# schematic.net
KiCad netlist of a schematic drawn in EAGLE
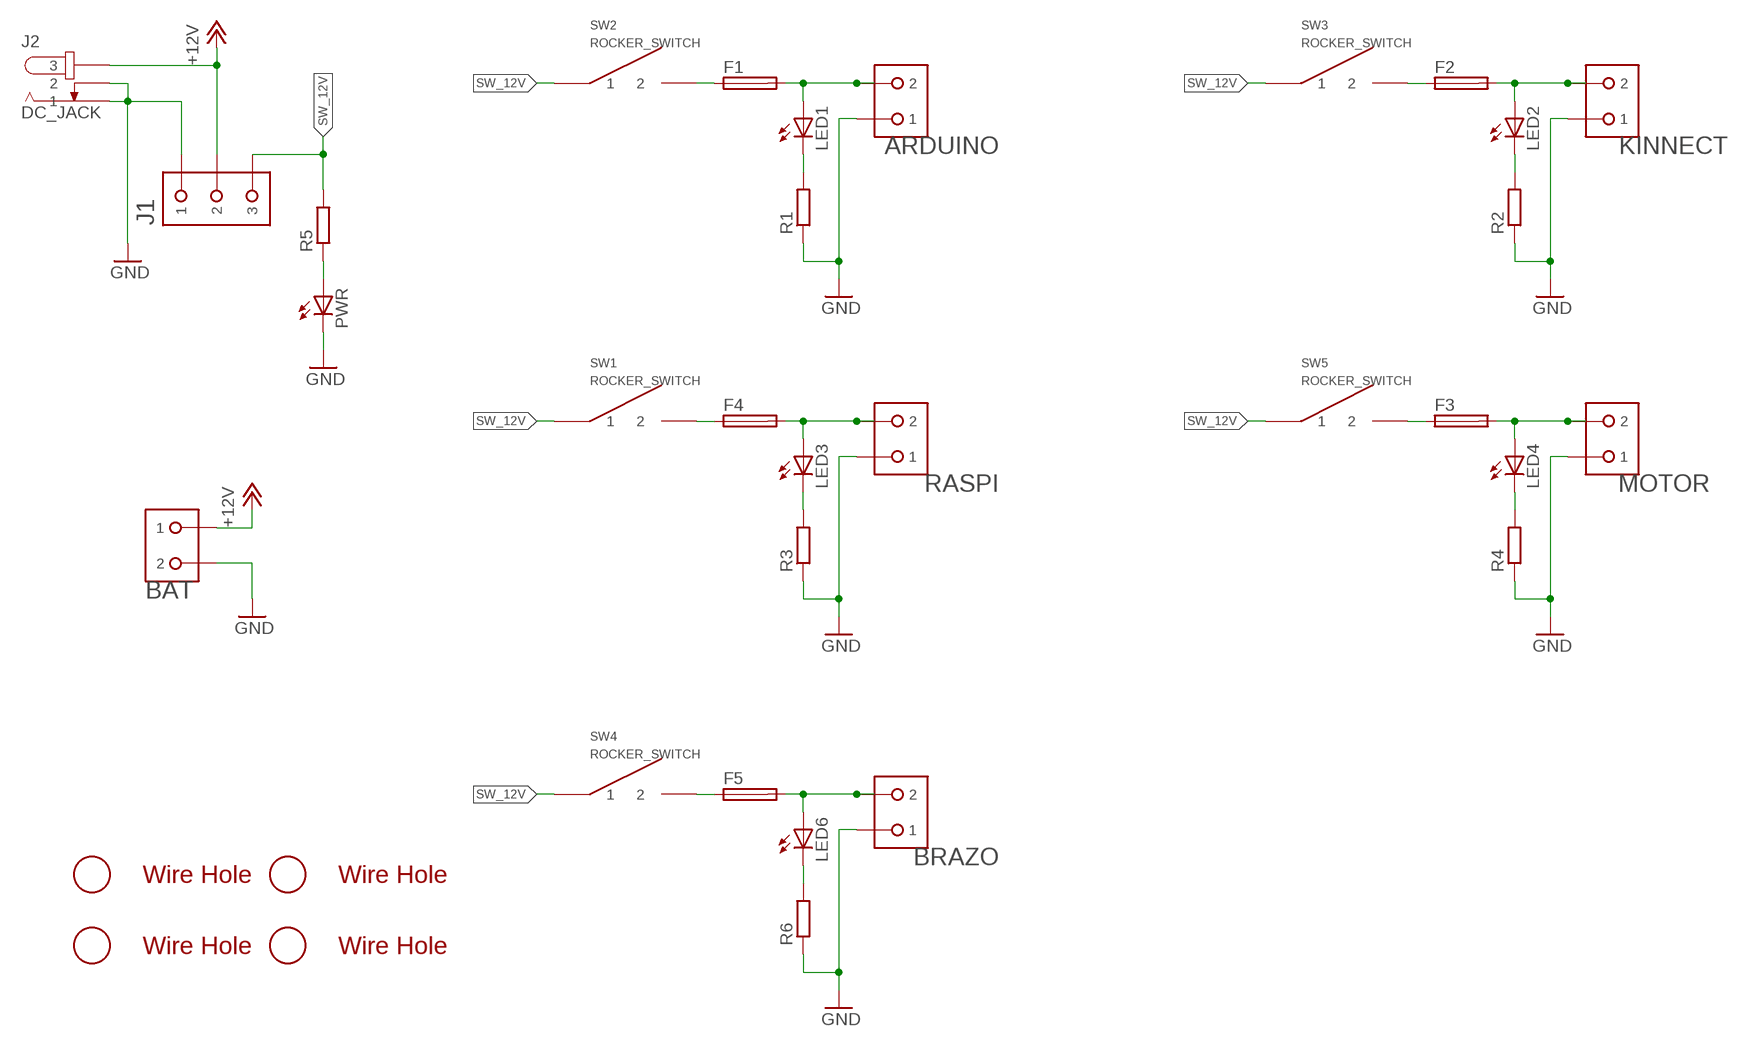
[diagram p0: schematic, sheet 1]

(export (version "E")
  (design (tool "Eeschema 10.0.6"))
  (components
    (comp (ref "ARDUINO")
      (value "B2P-VH(LF)(SN)")
      (footprint "eagle-import:B2P")
      (libsource (lib "eagle-import") (part "B2P?-VH(LF)(SN)"))
    )
    (comp (ref "BAT")
      (value "B2P-VH(LF)(SN)")
      (footprint "eagle-import:B2P")
      (libsource (lib "eagle-import") (part "B2P?-VH(LF)(SN)"))
    )
    (comp (ref "BRAZO")
      (value "B2P-VH(LF)(SN)")
      (footprint "eagle-import:B2P")
      (libsource (lib "eagle-import") (part "B2P?-VH(LF)(SN)"))
    )
    (comp (ref "F1")
      (value "FUSETE5")
      (footprint "eagle-import:TE5")
      (libsource (lib "eagle-import") (part "FUSETE5"))
    )
    (comp (ref "F2")
      (value "FUSETE5")
      (footprint "eagle-import:TE5")
      (libsource (lib "eagle-import") (part "FUSETE5"))
    )
    (comp (ref "F3")
      (value "FUSETE5")
      (footprint "eagle-import:TE5")
      (libsource (lib "eagle-import") (part "FUSETE5"))
    )
    (comp (ref "F4")
      (value "FUSETE5")
      (footprint "eagle-import:TE5")
      (libsource (lib "eagle-import") (part "FUSETE5"))
    )
    (comp (ref "F5")
      (value "FUSETE5")
      (footprint "eagle-import:TE5")
      (libsource (lib "eagle-import") (part "FUSETE5"))
    )
    (comp (ref "J1")
      (value "B3P-VH")
      (footprint "eagle-import:B3P-VH")
      (libsource (lib "eagle-import") (part "B3P-VH"))
    )
    (comp (ref "J2")
      (value "DC_JACK")
      (footprint "eagle-import:DC_JACK")
      (libsource (lib "eagle-import") (part "DC_JACK"))
    )
    (comp (ref "KINNECT")
      (value "B2P-VH(LF)(SN)")
      (footprint "eagle-import:B2P")
      (libsource (lib "eagle-import") (part "B2P?-VH(LF)(SN)"))
    )
    (comp (ref "LED1")
      (value "LEDCHIP-LED0805")
      (footprint "eagle-import:CHIP-LED0805")
      (libsource (lib "eagle-import") (part "LEDCHIP-LED0805"))
    )
    (comp (ref "LED2")
      (value "LEDCHIP-LED0805")
      (footprint "eagle-import:CHIP-LED0805")
      (libsource (lib "eagle-import") (part "LEDCHIP-LED0805"))
    )
    (comp (ref "LED3")
      (value "LEDCHIP-LED0805")
      (footprint "eagle-import:CHIP-LED0805")
      (libsource (lib "eagle-import") (part "LEDCHIP-LED0805"))
    )
    (comp (ref "LED4")
      (value "LEDCHIP-LED0805")
      (footprint "eagle-import:CHIP-LED0805")
      (libsource (lib "eagle-import") (part "LEDCHIP-LED0805"))
    )
    (comp (ref "LED6")
      (value "LEDCHIP-LED0805")
      (footprint "eagle-import:CHIP-LED0805")
      (libsource (lib "eagle-import") (part "LEDCHIP-LED0805"))
    )
    (comp (ref "MOTOR")
      (value "B2P-VH(LF)(SN)")
      (footprint "eagle-import:B2P")
      (libsource (lib "eagle-import") (part "B2P?-VH(LF)(SN)"))
    )
    (comp (ref "PWR")
      (value "LED3MM")
      (footprint "eagle-import:LED3MM")
      (libsource (lib "eagle-import") (part "led_LED3MM"))
    )
    (comp (ref "R1")
      (value "R-EU_R0805")
      (footprint "eagle-import:R0805")
      (libsource (lib "eagle-import") (part "R-EU_R0805"))
    )
    (comp (ref "R2")
      (value "R-EU_R0805")
      (footprint "eagle-import:R0805")
      (libsource (lib "eagle-import") (part "R-EU_R0805"))
    )
    (comp (ref "R3")
      (value "R-EU_R0805")
      (footprint "eagle-import:R0805")
      (libsource (lib "eagle-import") (part "R-EU_R0805"))
    )
    (comp (ref "R4")
      (value "R-EU_R0805")
      (footprint "eagle-import:R0805")
      (libsource (lib "eagle-import") (part "R-EU_R0805"))
    )
    (comp (ref "R5")
      (value "R-EU_R0805")
      (footprint "eagle-import:R0805")
      (libsource (lib "eagle-import") (part "R-EU_R0805"))
    )
    (comp (ref "R6")
      (value "R-EU_R0805")
      (footprint "eagle-import:R0805")
      (libsource (lib "eagle-import") (part "R-EU_R0805"))
    )
    (comp (ref "RASPI")
      (value "B2P-VH(LF)(SN)")
      (footprint "eagle-import:B2P")
      (libsource (lib "eagle-import") (part "B2P?-VH(LF)(SN)"))
    )
    (comp (ref "SW1")
      (value "ROCKER_SWITCH")
      (footprint "eagle-import:ROCKER_SWITCH")
      (libsource (lib "eagle-import") (part "ROCKER_SWITCH"))
    )
    (comp (ref "SW2")
      (value "ROCKER_SWITCH")
      (footprint "eagle-import:ROCKER_SWITCH")
      (libsource (lib "eagle-import") (part "ROCKER_SWITCH"))
    )
    (comp (ref "SW3")
      (value "ROCKER_SWITCH")
      (footprint "eagle-import:ROCKER_SWITCH")
      (libsource (lib "eagle-import") (part "ROCKER_SWITCH"))
    )
    (comp (ref "SW4")
      (value "ROCKER_SWITCH")
      (footprint "eagle-import:ROCKER_SWITCH")
      (libsource (lib "eagle-import") (part "ROCKER_SWITCH"))
    )
    (comp (ref "SW5")
      (value "ROCKER_SWITCH")
      (footprint "eagle-import:ROCKER_SWITCH")
      (libsource (lib "eagle-import") (part "ROCKER_SWITCH"))
    )
    (comp (ref "U$1")
      (value "3MMHOLE")
      (footprint "eagle-import:3MMHOLE")
      (libsource (lib "eagle-import") (part "3MMHOLE"))
    )
    (comp (ref "U$3")
      (value "3MMHOLE")
      (footprint "eagle-import:3MMHOLE")
      (libsource (lib "eagle-import") (part "3MMHOLE"))
    )
    (comp (ref "U$4")
      (value "3MMHOLE")
      (footprint "eagle-import:3MMHOLE")
      (libsource (lib "eagle-import") (part "3MMHOLE"))
    )
    (comp (ref "U$5")
      (value "3MMHOLE")
      (footprint "eagle-import:3MMHOLE")
      (libsource (lib "eagle-import") (part "3MMHOLE"))
    )
  )
  (nets
    (net (code "1") (name "+12V") (class "Default")
      (node (ref "BAT") (pin "1") (pinfunction "1_1") (pintype "passive"))
      (node (ref "J1") (pin "2") (pinfunction "2_2") (pintype "passive"))
      (node (ref "J2") (pin "2") (pinfunction "3_2") (pintype "passive"))
      (node (ref "J2") (pin "8") (pinfunction "3_8") (pintype "passive"))
      (node (ref "J2") (pin "9") (pinfunction "3_9") (pintype "passive"))
    )
    (net (code "2") (name "GND") (class "Default")
      (node (ref "ARDUINO") (pin "1") (pinfunction "1_1") (pintype "passive"))
      (node (ref "BAT") (pin "2") (pinfunction "2_2") (pintype "passive"))
      (node (ref "BRAZO") (pin "1") (pinfunction "1_1") (pintype "passive"))
      (node (ref "J1") (pin "1") (pinfunction "1_1") (pintype "passive"))
      (node (ref "J2") (pin "1") (pinfunction "2_1") (pintype "passive"))
      (node (ref "J2") (pin "3") (pinfunction "1_3") (pintype "passive"))
      (node (ref "J2") (pin "4") (pinfunction "2_4") (pintype "passive"))
      (node (ref "J2") (pin "5") (pinfunction "2_5") (pintype "passive"))
      (node (ref "J2") (pin "6") (pinfunction "1_6") (pintype "passive"))
      (node (ref "J2") (pin "7") (pinfunction "1_7") (pintype "passive"))
      (node (ref "KINNECT") (pin "1") (pinfunction "1_1") (pintype "passive"))
      (node (ref "MOTOR") (pin "1") (pinfunction "1_1") (pintype "passive"))
      (node (ref "PWR") (pin "K") (pinfunction "C_K") (pintype "passive"))
      (node (ref "R1") (pin "1") (pinfunction "1_1") (pintype "passive"))
      (node (ref "R2") (pin "1") (pinfunction "1_1") (pintype "passive"))
      (node (ref "R3") (pin "1") (pinfunction "1_1") (pintype "passive"))
      (node (ref "R4") (pin "1") (pinfunction "1_1") (pintype "passive"))
      (node (ref "R6") (pin "1") (pinfunction "1_1") (pintype "passive"))
      (node (ref "RASPI") (pin "1") (pinfunction "1_1") (pintype "passive"))
    )
    (net (code "3") (name "Net-(ARDUINO-Pad2)") (class "Default")
      (node (ref "ARDUINO") (pin "2") (pinfunction "2_2") (pintype "passive"))
      (node (ref "F1") (pin "2") (pinfunction "2_2") (pintype "passive"))
      (node (ref "LED1") (pin "A") (pinfunction "A_A") (pintype "passive"))
    )
    (net (code "4") (name "Net-(BRAZO-Pad2)") (class "Default")
      (node (ref "BRAZO") (pin "2") (pinfunction "2_2") (pintype "passive"))
      (node (ref "F5") (pin "2") (pinfunction "2_2") (pintype "passive"))
      (node (ref "LED6") (pin "A") (pinfunction "A_A") (pintype "passive"))
    )
    (net (code "5") (name "Net-(F1-Pad1)") (class "Default")
      (node (ref "F1") (pin "1") (pinfunction "1_1") (pintype "passive"))
      (node (ref "SW2") (pin "P$12") (pinfunction "2_P$12") (pintype "passive"))
      (node (ref "SW2") (pin "P$13") (pinfunction "2_P$13") (pintype "passive"))
      (node (ref "SW2") (pin "P$14") (pinfunction "2_P$14") (pintype "passive"))
      (node (ref "SW2") (pin "P$15") (pinfunction "2_P$15") (pintype "passive"))
      (node (ref "SW2") (pin "P$16") (pinfunction "2_P$16") (pintype "passive"))
      (node (ref "SW2") (pin "P$17") (pinfunction "2_P$17") (pintype "passive"))
      (node (ref "SW2") (pin "P$18") (pinfunction "2_P$18") (pintype "passive"))
      (node (ref "SW2") (pin "P$19") (pinfunction "2_P$19") (pintype "passive"))
      (node (ref "SW2") (pin "P$20") (pinfunction "2_P$20") (pintype "passive"))
      (node (ref "SW2") (pin "P$21") (pinfunction "2_P$21") (pintype "passive"))
      (node (ref "SW2") (pin "P$22") (pinfunction "2_P$22") (pintype "passive"))
    )
    (net (code "6") (name "Net-(F2-Pad1)") (class "Default")
      (node (ref "F2") (pin "1") (pinfunction "1_1") (pintype "passive"))
      (node (ref "SW3") (pin "P$12") (pinfunction "2_P$12") (pintype "passive"))
      (node (ref "SW3") (pin "P$13") (pinfunction "2_P$13") (pintype "passive"))
      (node (ref "SW3") (pin "P$14") (pinfunction "2_P$14") (pintype "passive"))
      (node (ref "SW3") (pin "P$15") (pinfunction "2_P$15") (pintype "passive"))
      (node (ref "SW3") (pin "P$16") (pinfunction "2_P$16") (pintype "passive"))
      (node (ref "SW3") (pin "P$17") (pinfunction "2_P$17") (pintype "passive"))
      (node (ref "SW3") (pin "P$18") (pinfunction "2_P$18") (pintype "passive"))
      (node (ref "SW3") (pin "P$19") (pinfunction "2_P$19") (pintype "passive"))
      (node (ref "SW3") (pin "P$20") (pinfunction "2_P$20") (pintype "passive"))
      (node (ref "SW3") (pin "P$21") (pinfunction "2_P$21") (pintype "passive"))
      (node (ref "SW3") (pin "P$22") (pinfunction "2_P$22") (pintype "passive"))
    )
    (net (code "7") (name "Net-(F2-Pad2)") (class "Default")
      (node (ref "F2") (pin "2") (pinfunction "2_2") (pintype "passive"))
      (node (ref "KINNECT") (pin "2") (pinfunction "2_2") (pintype "passive"))
      (node (ref "LED2") (pin "A") (pinfunction "A_A") (pintype "passive"))
    )
    (net (code "8") (name "Net-(F3-Pad1)") (class "Default")
      (node (ref "F3") (pin "1") (pinfunction "1_1") (pintype "passive"))
      (node (ref "SW5") (pin "P$12") (pinfunction "2_P$12") (pintype "passive"))
      (node (ref "SW5") (pin "P$13") (pinfunction "2_P$13") (pintype "passive"))
      (node (ref "SW5") (pin "P$14") (pinfunction "2_P$14") (pintype "passive"))
      (node (ref "SW5") (pin "P$15") (pinfunction "2_P$15") (pintype "passive"))
      (node (ref "SW5") (pin "P$16") (pinfunction "2_P$16") (pintype "passive"))
      (node (ref "SW5") (pin "P$17") (pinfunction "2_P$17") (pintype "passive"))
      (node (ref "SW5") (pin "P$18") (pinfunction "2_P$18") (pintype "passive"))
      (node (ref "SW5") (pin "P$19") (pinfunction "2_P$19") (pintype "passive"))
      (node (ref "SW5") (pin "P$20") (pinfunction "2_P$20") (pintype "passive"))
      (node (ref "SW5") (pin "P$21") (pinfunction "2_P$21") (pintype "passive"))
      (node (ref "SW5") (pin "P$22") (pinfunction "2_P$22") (pintype "passive"))
    )
    (net (code "9") (name "Net-(F3-Pad2)") (class "Default")
      (node (ref "F3") (pin "2") (pinfunction "2_2") (pintype "passive"))
      (node (ref "LED4") (pin "A") (pinfunction "A_A") (pintype "passive"))
      (node (ref "MOTOR") (pin "2") (pinfunction "2_2") (pintype "passive"))
    )
    (net (code "10") (name "Net-(F4-Pad1)") (class "Default")
      (node (ref "F4") (pin "1") (pinfunction "1_1") (pintype "passive"))
      (node (ref "SW1") (pin "P$12") (pinfunction "2_P$12") (pintype "passive"))
      (node (ref "SW1") (pin "P$13") (pinfunction "2_P$13") (pintype "passive"))
      (node (ref "SW1") (pin "P$14") (pinfunction "2_P$14") (pintype "passive"))
      (node (ref "SW1") (pin "P$15") (pinfunction "2_P$15") (pintype "passive"))
      (node (ref "SW1") (pin "P$16") (pinfunction "2_P$16") (pintype "passive"))
      (node (ref "SW1") (pin "P$17") (pinfunction "2_P$17") (pintype "passive"))
      (node (ref "SW1") (pin "P$18") (pinfunction "2_P$18") (pintype "passive"))
      (node (ref "SW1") (pin "P$19") (pinfunction "2_P$19") (pintype "passive"))
      (node (ref "SW1") (pin "P$20") (pinfunction "2_P$20") (pintype "passive"))
      (node (ref "SW1") (pin "P$21") (pinfunction "2_P$21") (pintype "passive"))
      (node (ref "SW1") (pin "P$22") (pinfunction "2_P$22") (pintype "passive"))
    )
    (net (code "11") (name "Net-(F4-Pad2)") (class "Default")
      (node (ref "F4") (pin "2") (pinfunction "2_2") (pintype "passive"))
      (node (ref "LED3") (pin "A") (pinfunction "A_A") (pintype "passive"))
      (node (ref "RASPI") (pin "2") (pinfunction "2_2") (pintype "passive"))
    )
    (net (code "12") (name "Net-(F5-Pad1)") (class "Default")
      (node (ref "F5") (pin "1") (pinfunction "1_1") (pintype "passive"))
      (node (ref "SW4") (pin "P$12") (pinfunction "2_P$12") (pintype "passive"))
      (node (ref "SW4") (pin "P$13") (pinfunction "2_P$13") (pintype "passive"))
      (node (ref "SW4") (pin "P$14") (pinfunction "2_P$14") (pintype "passive"))
      (node (ref "SW4") (pin "P$15") (pinfunction "2_P$15") (pintype "passive"))
      (node (ref "SW4") (pin "P$16") (pinfunction "2_P$16") (pintype "passive"))
      (node (ref "SW4") (pin "P$17") (pinfunction "2_P$17") (pintype "passive"))
      (node (ref "SW4") (pin "P$18") (pinfunction "2_P$18") (pintype "passive"))
      (node (ref "SW4") (pin "P$19") (pinfunction "2_P$19") (pintype "passive"))
      (node (ref "SW4") (pin "P$20") (pinfunction "2_P$20") (pintype "passive"))
      (node (ref "SW4") (pin "P$21") (pinfunction "2_P$21") (pintype "passive"))
      (node (ref "SW4") (pin "P$22") (pinfunction "2_P$22") (pintype "passive"))
    )
    (net (code "13") (name "Net-(LED1-PadC)") (class "Default")
      (node (ref "LED1") (pin "C") (pinfunction "C_C") (pintype "passive"))
      (node (ref "R1") (pin "2") (pinfunction "2_2") (pintype "passive"))
    )
    (net (code "14") (name "Net-(LED2-PadC)") (class "Default")
      (node (ref "LED2") (pin "C") (pinfunction "C_C") (pintype "passive"))
      (node (ref "R2") (pin "2") (pinfunction "2_2") (pintype "passive"))
    )
    (net (code "15") (name "Net-(LED3-PadC)") (class "Default")
      (node (ref "LED3") (pin "C") (pinfunction "C_C") (pintype "passive"))
      (node (ref "R3") (pin "2") (pinfunction "2_2") (pintype "passive"))
    )
    (net (code "16") (name "Net-(LED4-PadC)") (class "Default")
      (node (ref "LED4") (pin "C") (pinfunction "C_C") (pintype "passive"))
      (node (ref "R4") (pin "2") (pinfunction "2_2") (pintype "passive"))
    )
    (net (code "17") (name "Net-(LED6-PadC)") (class "Default")
      (node (ref "LED6") (pin "C") (pinfunction "C_C") (pintype "passive"))
      (node (ref "R6") (pin "2") (pinfunction "2_2") (pintype "passive"))
    )
    (net (code "18") (name "Net-(PWR-PadA)") (class "Default")
      (node (ref "PWR") (pin "A") (pinfunction "A_A") (pintype "passive"))
      (node (ref "R5") (pin "1") (pinfunction "1_1") (pintype "passive"))
    )
    (net (code "19") (name "SW_12V") (class "Default")
      (node (ref "J1") (pin "3") (pinfunction "3_3") (pintype "passive"))
      (node (ref "R5") (pin "2") (pinfunction "2_2") (pintype "passive"))
      (node (ref "SW1") (pin "P$1") (pinfunction "1_P$1") (pintype "passive"))
      (node (ref "SW1") (pin "P$10") (pinfunction "1_P$10") (pintype "passive"))
      (node (ref "SW1") (pin "P$11") (pinfunction "1_P$11") (pintype "passive"))
      (node (ref "SW1") (pin "P$2") (pinfunction "1_P$2") (pintype "passive"))
      (node (ref "SW1") (pin "P$3") (pinfunction "1_P$3") (pintype "passive"))
      (node (ref "SW1") (pin "P$4") (pinfunction "1_P$4") (pintype "passive"))
      (node (ref "SW1") (pin "P$5") (pinfunction "1_P$5") (pintype "passive"))
      (node (ref "SW1") (pin "P$6") (pinfunction "1_P$6") (pintype "passive"))
      (node (ref "SW1") (pin "P$7") (pinfunction "1_P$7") (pintype "passive"))
      (node (ref "SW1") (pin "P$8") (pinfunction "1_P$8") (pintype "passive"))
      (node (ref "SW1") (pin "P$9") (pinfunction "1_P$9") (pintype "passive"))
      (node (ref "SW2") (pin "P$1") (pinfunction "1_P$1") (pintype "passive"))
      (node (ref "SW2") (pin "P$10") (pinfunction "1_P$10") (pintype "passive"))
      (node (ref "SW2") (pin "P$11") (pinfunction "1_P$11") (pintype "passive"))
      (node (ref "SW2") (pin "P$2") (pinfunction "1_P$2") (pintype "passive"))
      (node (ref "SW2") (pin "P$3") (pinfunction "1_P$3") (pintype "passive"))
      (node (ref "SW2") (pin "P$4") (pinfunction "1_P$4") (pintype "passive"))
      (node (ref "SW2") (pin "P$5") (pinfunction "1_P$5") (pintype "passive"))
      (node (ref "SW2") (pin "P$6") (pinfunction "1_P$6") (pintype "passive"))
      (node (ref "SW2") (pin "P$7") (pinfunction "1_P$7") (pintype "passive"))
      (node (ref "SW2") (pin "P$8") (pinfunction "1_P$8") (pintype "passive"))
      (node (ref "SW2") (pin "P$9") (pinfunction "1_P$9") (pintype "passive"))
      (node (ref "SW3") (pin "P$1") (pinfunction "1_P$1") (pintype "passive"))
      (node (ref "SW3") (pin "P$10") (pinfunction "1_P$10") (pintype "passive"))
      (node (ref "SW3") (pin "P$11") (pinfunction "1_P$11") (pintype "passive"))
      (node (ref "SW3") (pin "P$2") (pinfunction "1_P$2") (pintype "passive"))
      (node (ref "SW3") (pin "P$3") (pinfunction "1_P$3") (pintype "passive"))
      (node (ref "SW3") (pin "P$4") (pinfunction "1_P$4") (pintype "passive"))
      (node (ref "SW3") (pin "P$5") (pinfunction "1_P$5") (pintype "passive"))
      (node (ref "SW3") (pin "P$6") (pinfunction "1_P$6") (pintype "passive"))
      (node (ref "SW3") (pin "P$7") (pinfunction "1_P$7") (pintype "passive"))
      (node (ref "SW3") (pin "P$8") (pinfunction "1_P$8") (pintype "passive"))
      (node (ref "SW3") (pin "P$9") (pinfunction "1_P$9") (pintype "passive"))
      (node (ref "SW4") (pin "P$1") (pinfunction "1_P$1") (pintype "passive"))
      (node (ref "SW4") (pin "P$10") (pinfunction "1_P$10") (pintype "passive"))
      (node (ref "SW4") (pin "P$11") (pinfunction "1_P$11") (pintype "passive"))
      (node (ref "SW4") (pin "P$2") (pinfunction "1_P$2") (pintype "passive"))
      (node (ref "SW4") (pin "P$3") (pinfunction "1_P$3") (pintype "passive"))
      (node (ref "SW4") (pin "P$4") (pinfunction "1_P$4") (pintype "passive"))
      (node (ref "SW4") (pin "P$5") (pinfunction "1_P$5") (pintype "passive"))
      (node (ref "SW4") (pin "P$6") (pinfunction "1_P$6") (pintype "passive"))
      (node (ref "SW4") (pin "P$7") (pinfunction "1_P$7") (pintype "passive"))
      (node (ref "SW4") (pin "P$8") (pinfunction "1_P$8") (pintype "passive"))
      (node (ref "SW4") (pin "P$9") (pinfunction "1_P$9") (pintype "passive"))
      (node (ref "SW5") (pin "P$1") (pinfunction "1_P$1") (pintype "passive"))
      (node (ref "SW5") (pin "P$10") (pinfunction "1_P$10") (pintype "passive"))
      (node (ref "SW5") (pin "P$11") (pinfunction "1_P$11") (pintype "passive"))
      (node (ref "SW5") (pin "P$2") (pinfunction "1_P$2") (pintype "passive"))
      (node (ref "SW5") (pin "P$3") (pinfunction "1_P$3") (pintype "passive"))
      (node (ref "SW5") (pin "P$4") (pinfunction "1_P$4") (pintype "passive"))
      (node (ref "SW5") (pin "P$5") (pinfunction "1_P$5") (pintype "passive"))
      (node (ref "SW5") (pin "P$6") (pinfunction "1_P$6") (pintype "passive"))
      (node (ref "SW5") (pin "P$7") (pinfunction "1_P$7") (pintype "passive"))
      (node (ref "SW5") (pin "P$8") (pinfunction "1_P$8") (pintype "passive"))
      (node (ref "SW5") (pin "P$9") (pinfunction "1_P$9") (pintype "passive"))
    )
  )
)
